# 6_uart_esc_i2c.net
KiCad netlist of a schematic drawn in Altium Designer
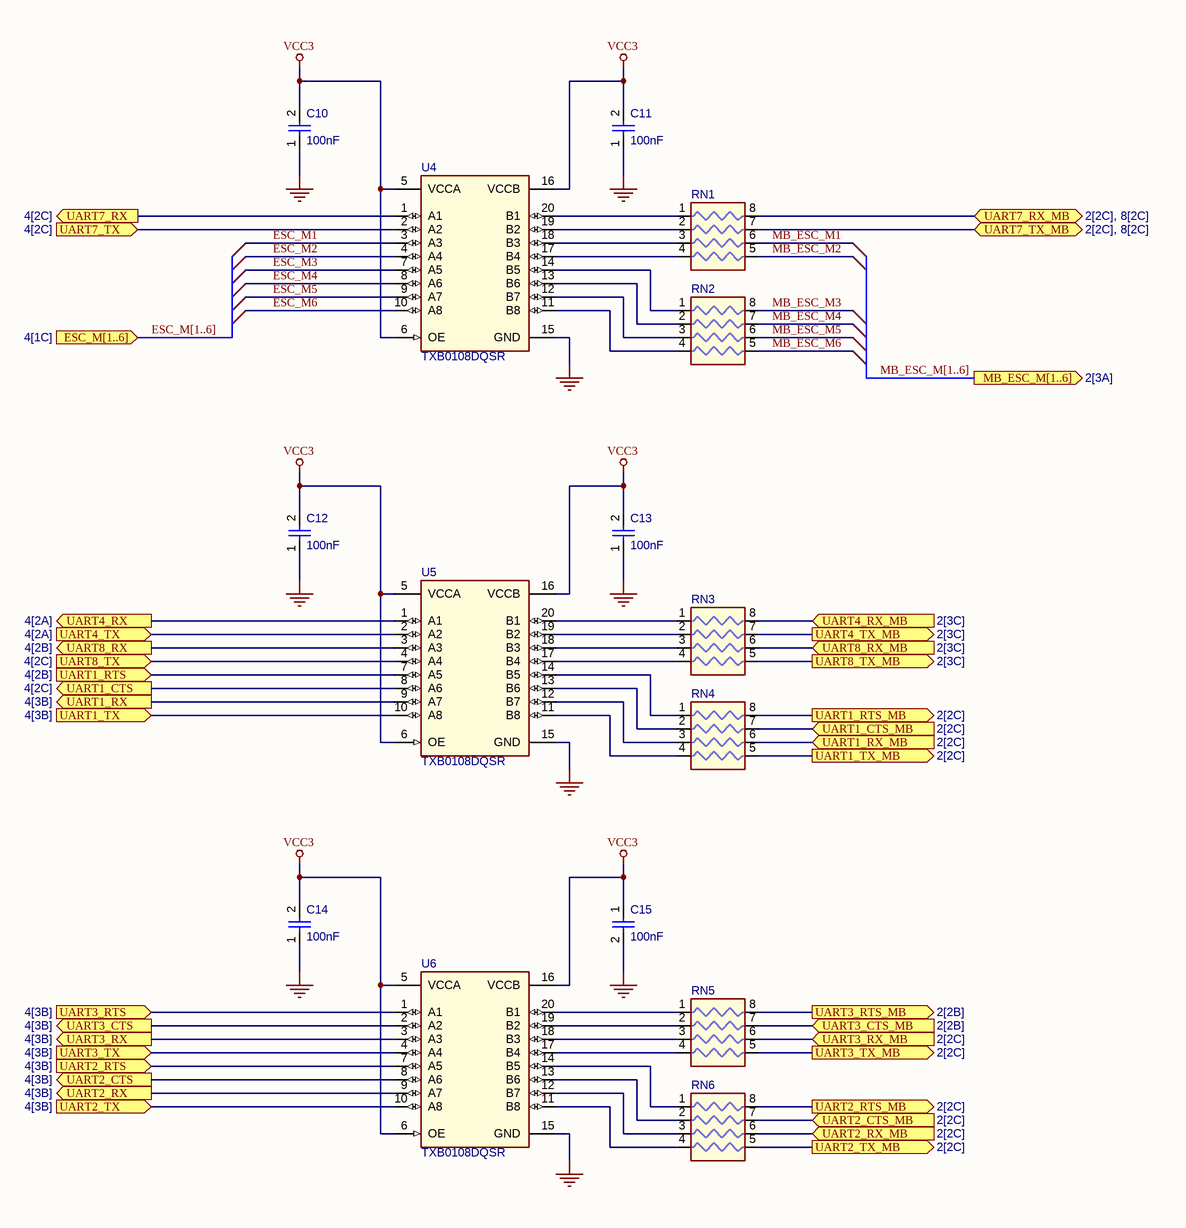
[diagram p0: 6_uart_esc_i2c.SchDoc]

(export (version "E")
  (design (tool "Eeschema 10.0.6"))
  (components
    (comp (ref "C10")
      (value "100nF")
      (footprint "CAPC0402(1005)60_L")
      (description "Chip Capacitor, 100nF +/-20%, 10V, 0402, Thickness 0.6 mm")
      (fields (field (name "TOLERANCE") "20%") (field (name "MANUFACTURER") "KEMET"))
      (libsource (lib "Kame_FMU") (part "Capacitor 100nF +/-20% 10V 0402"))
    )
    (comp (ref "C11")
      (value "100nF")
      (footprint "CAPC0402(1005)60_L")
      (description "Chip Capacitor, 100nF +/-20%, 10V, 0402, Thickness 0.6 mm")
      (fields (field (name "TOLERANCE") "20%") (field (name "MANUFACTURER") "KEMET"))
      (libsource (lib "Kame_FMU") (part "Capacitor 100nF +/-20% 10V 0402"))
    )
    (comp (ref "C12")
      (value "100nF")
      (footprint "CAPC0402(1005)60_L")
      (description "Chip Capacitor, 100nF +/-20%, 10V, 0402, Thickness 0.6 mm")
      (fields (field (name "TOLERANCE") "20%") (field (name "MANUFACTURER") "KEMET"))
      (libsource (lib "Kame_FMU") (part "Capacitor 100nF +/-20% 10V 0402"))
    )
    (comp (ref "C13")
      (value "100nF")
      (footprint "CAPC0402(1005)60_L")
      (description "Chip Capacitor, 100nF +/-20%, 10V, 0402, Thickness 0.6 mm")
      (fields (field (name "TOLERANCE") "20%") (field (name "MANUFACTURER") "KEMET"))
      (libsource (lib "Kame_FMU") (part "Capacitor 100nF +/-20% 10V 0402"))
    )
    (comp (ref "C14")
      (value "100nF")
      (footprint "CAPC0402(1005)60_L")
      (description "Chip Capacitor, 100nF +/-20%, 10V, 0402, Thickness 0.6 mm")
      (fields (field (name "TOLERANCE") "20%") (field (name "MANUFACTURER") "KEMET"))
      (libsource (lib "Kame_FMU") (part "Capacitor 100nF +/-20% 10V 0402"))
    )
    (comp (ref "C15")
      (value "100nF")
      (footprint "CAPC0402(1005)60_L")
      (description "Chip Capacitor, 100nF +/-20%, 10V, 0402, Thickness 0.6 mm")
      (fields (field (name "TOLERANCE") "20%") (field (name "MANUFACTURER") "KEMET"))
      (libsource (lib "Kame_FMU") (part "Capacitor 100nF +/-20% 10V 0402"))
    )
    (comp (ref "RN1")
      (value "Resistor 200R +/-5% 0402 62.5 mW")
      (footprint "Panasonic_EXB28")
      (fields
        (field (name "TOLERANCE") "5%")
        (field (name "POWER") "62.5mW")
        (field (name "MANUFACTURER") "Panasonic")
      )
      (libsource (lib "Kame_FMU") (part "Resistor 200R +/-5% 0402 62.5 mW"))
    )
    (comp (ref "RN2")
      (value "Resistor 200R +/-5% 0402 62.5 mW")
      (footprint "Panasonic_EXB28")
      (fields
        (field (name "TOLERANCE") "5%")
        (field (name "POWER") "62.5mW")
        (field (name "MANUFACTURER") "Panasonic")
      )
      (libsource (lib "Kame_FMU") (part "Resistor 200R +/-5% 0402 62.5 mW"))
    )
    (comp (ref "RN3")
      (value "Resistor 200R +/-5% 0402 62.5 mW")
      (footprint "Panasonic_EXB28")
      (fields
        (field (name "TOLERANCE") "5%")
        (field (name "POWER") "62.5mW")
        (field (name "MANUFACTURER") "Panasonic")
      )
      (libsource (lib "Kame_FMU") (part "Resistor 200R +/-5% 0402 62.5 mW"))
    )
    (comp (ref "RN4")
      (value "Resistor 200R +/-5% 0402 62.5 mW")
      (footprint "Panasonic_EXB28")
      (fields
        (field (name "TOLERANCE") "5%")
        (field (name "POWER") "62.5mW")
        (field (name "MANUFACTURER") "Panasonic")
      )
      (libsource (lib "Kame_FMU") (part "Resistor 200R +/-5% 0402 62.5 mW"))
    )
    (comp (ref "RN5")
      (value "Resistor 200R +/-5% 0402 62.5 mW")
      (footprint "Panasonic_EXB28")
      (fields
        (field (name "TOLERANCE") "5%")
        (field (name "POWER") "62.5mW")
        (field (name "MANUFACTURER") "Panasonic")
      )
      (libsource (lib "Kame_FMU") (part "Resistor 200R +/-5% 0402 62.5 mW"))
    )
    (comp (ref "RN6")
      (value "Resistor 200R +/-5% 0402 62.5 mW")
      (footprint "Panasonic_EXB28")
      (fields
        (field (name "TOLERANCE") "5%")
        (field (name "POWER") "62.5mW")
        (field (name "MANUFACTURER") "Panasonic")
      )
      (libsource (lib "Kame_FMU") (part "Resistor 200R +/-5% 0402 62.5 mW"))
    )
    (comp (ref "U4")
      (value "TXB0108DQSR")
      (footprint "DQS0020A_V")
      (fields (field (name "MANUFACTURER") "Texas Instruments"))
      (libsource (lib "Kame_FMU") (part "TXB0108DQSR"))
    )
    (comp (ref "U5")
      (value "TXB0108DQSR")
      (footprint "DQS0020A_V")
      (fields (field (name "MANUFACTURER") "Texas Instruments"))
      (libsource (lib "Kame_FMU") (part "TXB0108DQSR"))
    )
    (comp (ref "U6")
      (value "TXB0108DQSR")
      (footprint "DQS0020A_V")
      (fields (field (name "MANUFACTURER") "Texas Instruments"))
      (libsource (lib "Kame_FMU") (part "TXB0108DQSR"))
    )
  )
  (nets
    (net (code "1") (name "/ESC_M1") (class "Default")
      (node (ref "U4") (pin "3") (pinfunction "A3_3") (pintype "bidirectional"))
    )
    (net (code "2") (name "/ESC_M2") (class "Default")
      (node (ref "U4") (pin "4") (pinfunction "A4_4") (pintype "bidirectional"))
    )
    (net (code "3") (name "/ESC_M3") (class "Default")
      (node (ref "U4") (pin "7") (pinfunction "A5_7") (pintype "bidirectional"))
    )
    (net (code "4") (name "/ESC_M4") (class "Default")
      (node (ref "U4") (pin "8") (pinfunction "A6_8") (pintype "bidirectional"))
    )
    (net (code "5") (name "/ESC_M5") (class "Default")
      (node (ref "U4") (pin "9") (pinfunction "A7_9") (pintype "bidirectional"))
    )
    (net (code "6") (name "/ESC_M6") (class "Default")
      (node (ref "U4") (pin "10") (pinfunction "A8_10") (pintype "bidirectional"))
    )
    (net (code "8") (name "/MB_ESC_M1") (class "Default")
      (node (ref "RN1") (pin "6") (pinfunction "2_6") (pintype "passive"))
    )
    (net (code "9") (name "/MB_ESC_M2") (class "Default")
      (node (ref "RN1") (pin "5") (pinfunction "2_5") (pintype "passive"))
    )
    (net (code "10") (name "/MB_ESC_M3") (class "Default")
      (node (ref "RN2") (pin "8") (pinfunction "2_8") (pintype "passive"))
    )
    (net (code "11") (name "/MB_ESC_M4") (class "Default")
      (node (ref "RN2") (pin "7") (pinfunction "2_7") (pintype "passive"))
    )
    (net (code "12") (name "/MB_ESC_M5") (class "Default")
      (node (ref "RN2") (pin "6") (pinfunction "2_6") (pintype "passive"))
    )
    (net (code "13") (name "/MB_ESC_M6") (class "Default")
      (node (ref "RN2") (pin "5") (pinfunction "2_5") (pintype "passive"))
    )
    (net (code "15") (name "/UART1_CTS") (class "Default")
      (node (ref "U5") (pin "8") (pinfunction "A6_8") (pintype "bidirectional"))
    )
    (net (code "16") (name "/UART1_CTS_MB") (class "Default")
      (node (ref "RN4") (pin "7") (pinfunction "2_7") (pintype "passive"))
    )
    (net (code "17") (name "/UART1_RTS") (class "Default")
      (node (ref "U5") (pin "7") (pinfunction "A5_7") (pintype "bidirectional"))
    )
    (net (code "18") (name "/UART1_RTS_MB") (class "Default")
      (node (ref "RN4") (pin "8") (pinfunction "2_8") (pintype "passive"))
    )
    (net (code "19") (name "/UART1_RX") (class "Default")
      (node (ref "U5") (pin "9") (pinfunction "A7_9") (pintype "bidirectional"))
    )
    (net (code "20") (name "/UART1_RX_MB") (class "Default")
      (node (ref "RN4") (pin "6") (pinfunction "2_6") (pintype "passive"))
    )
    (net (code "21") (name "/UART1_TX") (class "Default")
      (node (ref "U5") (pin "10") (pinfunction "A8_10") (pintype "bidirectional"))
    )
    (net (code "22") (name "/UART1_TX_MB") (class "Default")
      (node (ref "RN4") (pin "5") (pinfunction "2_5") (pintype "passive"))
    )
    (net (code "23") (name "/UART2_CTS") (class "Default")
      (node (ref "U6") (pin "8") (pinfunction "A6_8") (pintype "bidirectional"))
    )
    (net (code "24") (name "/UART2_CTS_MB") (class "Default")
      (node (ref "RN6") (pin "7") (pinfunction "2_7") (pintype "passive"))
    )
    (net (code "25") (name "/UART2_RTS") (class "Default")
      (node (ref "U6") (pin "7") (pinfunction "A5_7") (pintype "bidirectional"))
    )
    (net (code "26") (name "/UART2_RTS_MB") (class "Default")
      (node (ref "RN6") (pin "8") (pinfunction "2_8") (pintype "passive"))
    )
    (net (code "27") (name "/UART2_RX") (class "Default")
      (node (ref "U6") (pin "9") (pinfunction "A7_9") (pintype "bidirectional"))
    )
    (net (code "28") (name "/UART2_RX_MB") (class "Default")
      (node (ref "RN6") (pin "6") (pinfunction "2_6") (pintype "passive"))
    )
    (net (code "29") (name "/UART2_TX") (class "Default")
      (node (ref "U6") (pin "10") (pinfunction "A8_10") (pintype "bidirectional"))
    )
    (net (code "30") (name "/UART2_TX_MB") (class "Default")
      (node (ref "RN6") (pin "5") (pinfunction "2_5") (pintype "passive"))
    )
    (net (code "31") (name "/UART3_CTS") (class "Default")
      (node (ref "U6") (pin "2") (pinfunction "A2_2") (pintype "bidirectional"))
    )
    (net (code "32") (name "/UART3_CTS_MB") (class "Default")
      (node (ref "RN5") (pin "7") (pinfunction "2_7") (pintype "passive"))
    )
    (net (code "33") (name "/UART3_RTS") (class "Default")
      (node (ref "U6") (pin "1") (pinfunction "A1_1") (pintype "bidirectional"))
    )
    (net (code "34") (name "/UART3_RTS_MB") (class "Default")
      (node (ref "RN5") (pin "8") (pinfunction "2_8") (pintype "passive"))
    )
    (net (code "35") (name "/UART3_RX") (class "Default")
      (node (ref "U6") (pin "3") (pinfunction "A3_3") (pintype "bidirectional"))
    )
    (net (code "36") (name "/UART3_RX_MB") (class "Default")
      (node (ref "RN5") (pin "6") (pinfunction "2_6") (pintype "passive"))
    )
    (net (code "37") (name "/UART3_TX") (class "Default")
      (node (ref "U6") (pin "4") (pinfunction "A4_4") (pintype "bidirectional"))
    )
    (net (code "38") (name "/UART3_TX_MB") (class "Default")
      (node (ref "RN5") (pin "5") (pinfunction "2_5") (pintype "passive"))
    )
    (net (code "39") (name "/UART4_RX") (class "Default")
      (node (ref "U5") (pin "1") (pinfunction "A1_1") (pintype "bidirectional"))
    )
    (net (code "40") (name "/UART4_RX_MB") (class "Default")
      (node (ref "RN3") (pin "8") (pinfunction "2_8") (pintype "passive"))
    )
    (net (code "41") (name "/UART4_TX") (class "Default")
      (node (ref "U5") (pin "2") (pinfunction "A2_2") (pintype "bidirectional"))
    )
    (net (code "42") (name "/UART4_TX_MB") (class "Default")
      (node (ref "RN3") (pin "7") (pinfunction "2_7") (pintype "passive"))
    )
    (net (code "43") (name "/UART7_RX") (class "Default")
      (node (ref "U4") (pin "1") (pinfunction "A1_1") (pintype "bidirectional"))
    )
    (net (code "44") (name "/UART7_RX_MB") (class "Default")
      (node (ref "RN1") (pin "8") (pinfunction "2_8") (pintype "passive"))
    )
    (net (code "45") (name "/UART7_TX") (class "Default")
      (node (ref "U4") (pin "2") (pinfunction "A2_2") (pintype "bidirectional"))
    )
    (net (code "46") (name "/UART7_TX_MB") (class "Default")
      (node (ref "RN1") (pin "7") (pinfunction "2_7") (pintype "passive"))
    )
    (net (code "47") (name "/UART8_RX") (class "Default")
      (node (ref "U5") (pin "3") (pinfunction "A3_3") (pintype "bidirectional"))
    )
    (net (code "48") (name "/UART8_RX_MB") (class "Default")
      (node (ref "RN3") (pin "6") (pinfunction "2_6") (pintype "passive"))
    )
    (net (code "49") (name "/UART8_TX") (class "Default")
      (node (ref "U5") (pin "4") (pinfunction "A4_4") (pintype "bidirectional"))
    )
    (net (code "50") (name "/UART8_TX_MB") (class "Default")
      (node (ref "RN3") (pin "5") (pinfunction "2_5") (pintype "passive"))
    )
    (net (code "51") (name "GND") (class "Default")
      (node (ref "C10") (pin "1") (pinfunction "1_1") (pintype "passive"))
      (node (ref "C11") (pin "1") (pinfunction "1_1") (pintype "passive"))
      (node (ref "C12") (pin "1") (pinfunction "1_1") (pintype "passive"))
      (node (ref "C13") (pin "1") (pinfunction "1_1") (pintype "passive"))
      (node (ref "C14") (pin "1") (pinfunction "1_1") (pintype "passive"))
      (node (ref "C15") (pin "2") (pinfunction "2_2") (pintype "passive"))
      (node (ref "U4") (pin "15") (pinfunction "GND_15") (pintype "power_in"))
      (node (ref "U5") (pin "15") (pinfunction "GND_15") (pintype "power_in"))
      (node (ref "U6") (pin "15") (pinfunction "GND_15") (pintype "power_in"))
    )
    (net (code "52") (name "Net-(U4-B1)") (class "Default")
      (node (ref "RN1") (pin "1") (pinfunction "1_1") (pintype "passive"))
      (node (ref "U4") (pin "20") (pinfunction "B1_20") (pintype "bidirectional"))
    )
    (net (code "53") (name "Net-(U4-B2)") (class "Default")
      (node (ref "RN1") (pin "2") (pinfunction "1_2") (pintype "passive"))
      (node (ref "U4") (pin "19") (pinfunction "B2_19") (pintype "bidirectional"))
    )
    (net (code "54") (name "Net-(U4-B3)") (class "Default")
      (node (ref "RN1") (pin "3") (pinfunction "1_3") (pintype "passive"))
      (node (ref "U4") (pin "18") (pinfunction "B3_18") (pintype "bidirectional"))
    )
    (net (code "55") (name "Net-(U4-B4)") (class "Default")
      (node (ref "RN1") (pin "4") (pinfunction "1_4") (pintype "passive"))
      (node (ref "U4") (pin "17") (pinfunction "B4_17") (pintype "bidirectional"))
    )
    (net (code "56") (name "Net-(U4-B5)") (class "Default")
      (node (ref "RN2") (pin "1") (pinfunction "1_1") (pintype "passive"))
      (node (ref "U4") (pin "14") (pinfunction "B5_14") (pintype "bidirectional"))
    )
    (net (code "57") (name "Net-(U4-B6)") (class "Default")
      (node (ref "RN2") (pin "2") (pinfunction "1_2") (pintype "passive"))
      (node (ref "U4") (pin "13") (pinfunction "B6_13") (pintype "bidirectional"))
    )
    (net (code "58") (name "Net-(U4-B7)") (class "Default")
      (node (ref "RN2") (pin "3") (pinfunction "1_3") (pintype "passive"))
      (node (ref "U4") (pin "12") (pinfunction "B7_12") (pintype "bidirectional"))
    )
    (net (code "59") (name "Net-(U4-B8)") (class "Default")
      (node (ref "RN2") (pin "4") (pinfunction "1_4") (pintype "passive"))
      (node (ref "U4") (pin "11") (pinfunction "B8_11") (pintype "bidirectional"))
    )
    (net (code "60") (name "Net-(U5-B1)") (class "Default")
      (node (ref "RN3") (pin "1") (pinfunction "1_1") (pintype "passive"))
      (node (ref "U5") (pin "20") (pinfunction "B1_20") (pintype "bidirectional"))
    )
    (net (code "61") (name "Net-(U5-B2)") (class "Default")
      (node (ref "RN3") (pin "2") (pinfunction "1_2") (pintype "passive"))
      (node (ref "U5") (pin "19") (pinfunction "B2_19") (pintype "bidirectional"))
    )
    (net (code "62") (name "Net-(U5-B3)") (class "Default")
      (node (ref "RN3") (pin "3") (pinfunction "1_3") (pintype "passive"))
      (node (ref "U5") (pin "18") (pinfunction "B3_18") (pintype "bidirectional"))
    )
    (net (code "63") (name "Net-(U5-B4)") (class "Default")
      (node (ref "RN3") (pin "4") (pinfunction "1_4") (pintype "passive"))
      (node (ref "U5") (pin "17") (pinfunction "B4_17") (pintype "bidirectional"))
    )
    (net (code "64") (name "Net-(U5-B5)") (class "Default")
      (node (ref "RN4") (pin "1") (pinfunction "1_1") (pintype "passive"))
      (node (ref "U5") (pin "14") (pinfunction "B5_14") (pintype "bidirectional"))
    )
    (net (code "65") (name "Net-(U5-B6)") (class "Default")
      (node (ref "RN4") (pin "2") (pinfunction "1_2") (pintype "passive"))
      (node (ref "U5") (pin "13") (pinfunction "B6_13") (pintype "bidirectional"))
    )
    (net (code "66") (name "Net-(U5-B7)") (class "Default")
      (node (ref "RN4") (pin "3") (pinfunction "1_3") (pintype "passive"))
      (node (ref "U5") (pin "12") (pinfunction "B7_12") (pintype "bidirectional"))
    )
    (net (code "67") (name "Net-(U5-B8)") (class "Default")
      (node (ref "RN4") (pin "4") (pinfunction "1_4") (pintype "passive"))
      (node (ref "U5") (pin "11") (pinfunction "B8_11") (pintype "bidirectional"))
    )
    (net (code "68") (name "Net-(U6-B1)") (class "Default")
      (node (ref "RN5") (pin "1") (pinfunction "1_1") (pintype "passive"))
      (node (ref "U6") (pin "20") (pinfunction "B1_20") (pintype "bidirectional"))
    )
    (net (code "69") (name "Net-(U6-B2)") (class "Default")
      (node (ref "RN5") (pin "2") (pinfunction "1_2") (pintype "passive"))
      (node (ref "U6") (pin "19") (pinfunction "B2_19") (pintype "bidirectional"))
    )
    (net (code "70") (name "Net-(U6-B3)") (class "Default")
      (node (ref "RN5") (pin "3") (pinfunction "1_3") (pintype "passive"))
      (node (ref "U6") (pin "18") (pinfunction "B3_18") (pintype "bidirectional"))
    )
    (net (code "71") (name "Net-(U6-B4)") (class "Default")
      (node (ref "RN5") (pin "4") (pinfunction "1_4") (pintype "passive"))
      (node (ref "U6") (pin "17") (pinfunction "B4_17") (pintype "bidirectional"))
    )
    (net (code "72") (name "Net-(U6-B5)") (class "Default")
      (node (ref "RN6") (pin "1") (pinfunction "1_1") (pintype "passive"))
      (node (ref "U6") (pin "14") (pinfunction "B5_14") (pintype "bidirectional"))
    )
    (net (code "73") (name "Net-(U6-B6)") (class "Default")
      (node (ref "RN6") (pin "2") (pinfunction "1_2") (pintype "passive"))
      (node (ref "U6") (pin "13") (pinfunction "B6_13") (pintype "bidirectional"))
    )
    (net (code "74") (name "Net-(U6-B7)") (class "Default")
      (node (ref "RN6") (pin "3") (pinfunction "1_3") (pintype "passive"))
      (node (ref "U6") (pin "12") (pinfunction "B7_12") (pintype "bidirectional"))
    )
    (net (code "75") (name "Net-(U6-B8)") (class "Default")
      (node (ref "RN6") (pin "4") (pinfunction "1_4") (pintype "passive"))
      (node (ref "U6") (pin "11") (pinfunction "B8_11") (pintype "bidirectional"))
    )
    (net (code "76") (name "VCC3") (class "Default")
      (node (ref "C10") (pin "2") (pinfunction "2_2") (pintype "passive"))
      (node (ref "C11") (pin "2") (pinfunction "2_2") (pintype "passive"))
      (node (ref "C12") (pin "2") (pinfunction "2_2") (pintype "passive"))
      (node (ref "C13") (pin "2") (pinfunction "2_2") (pintype "passive"))
      (node (ref "C14") (pin "2") (pinfunction "2_2") (pintype "passive"))
      (node (ref "C15") (pin "1") (pinfunction "1_1") (pintype "passive"))
      (node (ref "U4") (pin "16") (pinfunction "VCCB_16") (pintype "power_in"))
      (node (ref "U4") (pin "5") (pinfunction "VCCA_5") (pintype "power_in"))
      (node (ref "U4") (pin "6") (pinfunction "OE_6") (pintype "input"))
      (node (ref "U5") (pin "16") (pinfunction "VCCB_16") (pintype "power_in"))
      (node (ref "U5") (pin "5") (pinfunction "VCCA_5") (pintype "power_in"))
      (node (ref "U5") (pin "6") (pinfunction "OE_6") (pintype "input"))
      (node (ref "U6") (pin "16") (pinfunction "VCCB_16") (pintype "power_in"))
      (node (ref "U6") (pin "5") (pinfunction "VCCA_5") (pintype "power_in"))
      (node (ref "U6") (pin "6") (pinfunction "OE_6") (pintype "input"))
    )
  )
)
